# prechodka.net
KiCad netlist of a schematic drawn in EAGLE
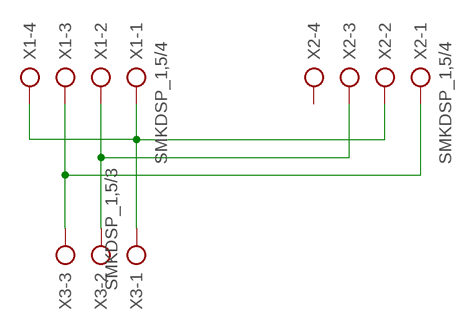
[diagram p0: schematic, sheet 1]

(export (version "E")
  (design (tool "Eeschema 10.0.6"))
  (components
    (comp (ref "X1")
      (value "SMKDSP_1,5/4")
      (footprint "eagle-import:SMKDSP_1,5_4")
      (fields (field (name "MF") "FARNELL") (field (name "MPN") "1733596"))
      (libsource (lib "eagle-import") (part "SMKDSP_1,5/4"))
    )
    (comp (ref "X2")
      (value "SMKDSP_1,5/4")
      (footprint "eagle-import:SMKDSP_1,5_4")
      (fields (field (name "MF") "FARNELL") (field (name "MPN") "1733596"))
      (libsource (lib "eagle-import") (part "SMKDSP_1,5/4"))
    )
    (comp (ref "X3")
      (value "SMKDSP_1,5/3")
      (footprint "eagle-import:SMKDSP_1,5_3")
      (fields (field (name "MF") "FARNELL") (field (name "MPN") "1733583"))
      (libsource (lib "eagle-import") (part "SMKDSP_1,5/3"))
    )
  )
  (nets
    (net (code "1") (name "Net-(X1A-KL)") (class "Default")
      (node (ref "X1") (pin "1") (pinfunction "KL_1") (pintype "passive"))
      (node (ref "X1") (pin "4") (pinfunction "KL_4") (pintype "passive"))
      (node (ref "X2") (pin "2") (pinfunction "KL_2") (pintype "passive"))
      (node (ref "X3") (pin "1") (pinfunction "KL_1") (pintype "passive"))
    )
    (net (code "2") (name "Net-(X1B-KL)") (class "Default")
      (node (ref "X1") (pin "2") (pinfunction "KL_2") (pintype "passive"))
      (node (ref "X2") (pin "3") (pinfunction "KL_3") (pintype "passive"))
      (node (ref "X3") (pin "2") (pinfunction "KL_2") (pintype "passive"))
    )
    (net (code "3") (name "Net-(X1C-KL)") (class "Default")
      (node (ref "X1") (pin "3") (pinfunction "KL_3") (pintype "passive"))
      (node (ref "X2") (pin "1") (pinfunction "KL_1") (pintype "passive"))
      (node (ref "X3") (pin "3") (pinfunction "KL_3") (pintype "passive"))
    )
    (net (code "4") (name "unconnected-(X2D-KL-Pad4)") (class "Default")
      (node (ref "X2") (pin "4") (pinfunction "KL_4") (pintype "passive"))
    )
  )
)
